# hidiot_1_0_final.net
KiCad netlist of a schematic drawn in EAGLE
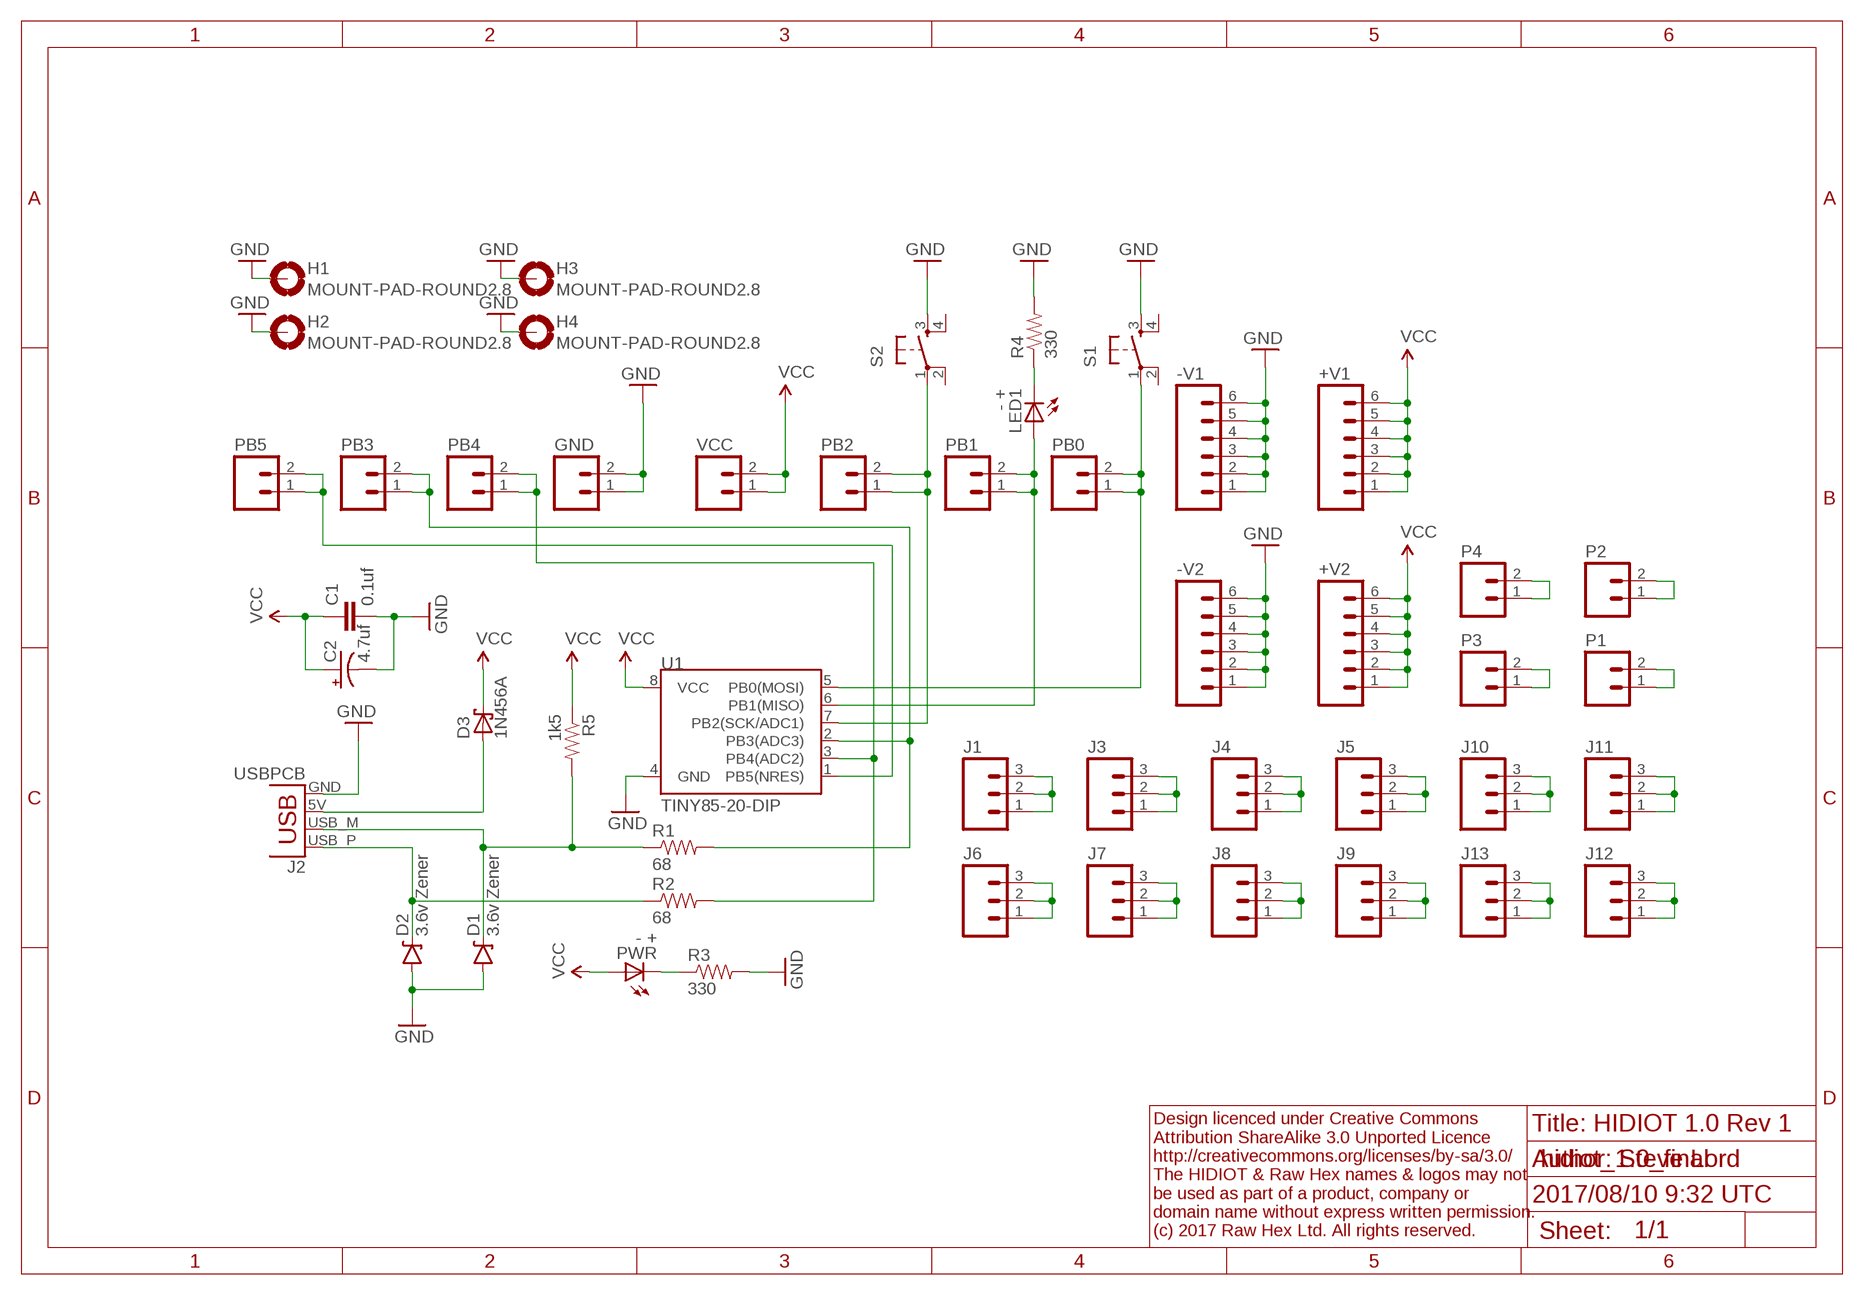
[diagram p0: schematic, sheet 1]

(export (version "E")
  (design (tool "Eeschema 10.0.6"))
  (components
    (comp (ref "+V1")
      (value "M06SILK_FEMALE_PTH")
      (footprint "eagle-import:1X06")
      (libsource (lib "eagle-import") (part "M06SILK_FEMALE_PTH"))
    )
    (comp (ref "+V2")
      (value "M06SILK_FEMALE_PTH")
      (footprint "eagle-import:1X06")
      (libsource (lib "eagle-import") (part "M06SILK_FEMALE_PTH"))
    )
    (comp (ref "-V1")
      (value "M06SILK_FEMALE_PTH")
      (footprint "eagle-import:1X06")
      (libsource (lib "eagle-import") (part "M06SILK_FEMALE_PTH"))
    )
    (comp (ref "-V2")
      (value "M06SILK_FEMALE_PTH")
      (footprint "eagle-import:1X06")
      (libsource (lib "eagle-import") (part "M06SILK_FEMALE_PTH"))
    )
    (comp (ref "C1")
      (value "0.1uf")
      (footprint "eagle-import:CAP-PTH-SMALL-KIT")
      (fields (field (name "MF") "VISHAY") (field (name "MPN") "K104K15X7RF5TH5"))
      (libsource (lib "eagle-import") (part "0.1UF-50V-20%(PTH)KIT-EZ"))
    )
    (comp (ref "C2")
      (value "4.7uf")
      (footprint "eagle-import:CPOL-RADIAL-100UF-25V")
      (fields (field (name "MF") "MULTICOMP") (field (name "MPN") "MCGPR50V475M5X11"))
      (libsource (lib "eagle-import") (part "100UF-25V-20%(PTH)"))
    )
    (comp (ref "D1")
      (value "3.6v Zener")
      (footprint "eagle-import:DIODE-ZENER")
      (fields (field (name "MF") "MULTICOMP") (field (name "MPN") "1N4729A"))
      (libsource (lib "eagle-import") (part "DIODE-ZENERPTH"))
    )
    (comp (ref "D2")
      (value "3.6v Zener")
      (footprint "eagle-import:DIODE-ZENER")
      (fields (field (name "MF") "MULTICOMP") (field (name "MPN") "1N4729A"))
      (libsource (lib "eagle-import") (part "DIODE-ZENERPTH"))
    )
    (comp (ref "D3")
      (value "1N456A")
      (footprint "eagle-import:DIODE_DO35-7")
      (fields (field (name "MF") "FAIRCHILD SEMICONDUCTOR"))
      (libsource (lib "eagle-import") (part "SCHOTTKY-DIODEDO35-7"))
    )
    (comp (ref "GND")
      (value "M02PTH")
      (footprint "eagle-import:1X02")
      (libsource (lib "eagle-import") (part "M02PTH"))
    )
    (comp (ref "H1")
      (value "MOUNT-PAD-ROUND2.8")
      (footprint "eagle-import:2,8-PAD")
      (libsource (lib "eagle-import") (part "MOUNT-PAD-ROUND2.8"))
    )
    (comp (ref "H2")
      (value "MOUNT-PAD-ROUND2.8")
      (footprint "eagle-import:2,8-PAD")
      (libsource (lib "eagle-import") (part "MOUNT-PAD-ROUND2.8"))
    )
    (comp (ref "H3")
      (value "MOUNT-PAD-ROUND2.8")
      (footprint "eagle-import:2,8-PAD")
      (libsource (lib "eagle-import") (part "MOUNT-PAD-ROUND2.8"))
    )
    (comp (ref "H4")
      (value "MOUNT-PAD-ROUND2.8")
      (footprint "eagle-import:2,8-PAD")
      (libsource (lib "eagle-import") (part "MOUNT-PAD-ROUND2.8"))
    )
    (comp (ref "J1")
      (value "M03PTH")
      (footprint "eagle-import:1X03")
      (libsource (lib "eagle-import") (part "M03PTH"))
    )
    (comp (ref "J2")
      (value "USBPCB")
      (footprint "eagle-import:USB-A-PCB")
      (libsource (lib "eagle-import") (part "USBPCB"))
    )
    (comp (ref "J3")
      (value "M03PTH")
      (footprint "eagle-import:1X03")
      (libsource (lib "eagle-import") (part "M03PTH"))
    )
    (comp (ref "J4")
      (value "M03PTH")
      (footprint "eagle-import:1X03")
      (libsource (lib "eagle-import") (part "M03PTH"))
    )
    (comp (ref "J5")
      (value "M03PTH")
      (footprint "eagle-import:1X03")
      (libsource (lib "eagle-import") (part "M03PTH"))
    )
    (comp (ref "J6")
      (value "M03PTH")
      (footprint "eagle-import:1X03")
      (libsource (lib "eagle-import") (part "M03PTH"))
    )
    (comp (ref "J7")
      (value "M03PTH")
      (footprint "eagle-import:1X03")
      (libsource (lib "eagle-import") (part "M03PTH"))
    )
    (comp (ref "J8")
      (value "M03PTH")
      (footprint "eagle-import:1X03")
      (libsource (lib "eagle-import") (part "M03PTH"))
    )
    (comp (ref "J9")
      (value "M03PTH")
      (footprint "eagle-import:1X03")
      (libsource (lib "eagle-import") (part "M03PTH"))
    )
    (comp (ref "J10")
      (value "M03PTH")
      (footprint "eagle-import:1X03")
      (libsource (lib "eagle-import") (part "M03PTH"))
    )
    (comp (ref "J11")
      (value "M03PTH")
      (footprint "eagle-import:1X03")
      (libsource (lib "eagle-import") (part "M03PTH"))
    )
    (comp (ref "J12")
      (value "M03PTH")
      (footprint "eagle-import:1X03")
      (libsource (lib "eagle-import") (part "M03PTH"))
    )
    (comp (ref "J13")
      (value "M03PTH")
      (footprint "eagle-import:1X03")
      (libsource (lib "eagle-import") (part "M03PTH"))
    )
    (comp (ref "LED1")
      (value "- +")
      (footprint "eagle-import:LED3MM")
      (fields (field (name "MF") "AVAGO TECHNOLOGIES") (field (name "MPN") "HLMP-K150"))
      (libsource (lib "eagle-import") (part "LED3MM"))
    )
    (comp (ref "P1")
      (value "M02PTH")
      (footprint "eagle-import:1X02")
      (libsource (lib "eagle-import") (part "M02PTH"))
    )
    (comp (ref "P2")
      (value "M02PTH")
      (footprint "eagle-import:1X02")
      (libsource (lib "eagle-import") (part "M02PTH"))
    )
    (comp (ref "P3")
      (value "M02PTH")
      (footprint "eagle-import:1X02")
      (libsource (lib "eagle-import") (part "M02PTH"))
    )
    (comp (ref "P4")
      (value "M02PTH")
      (footprint "eagle-import:1X02")
      (libsource (lib "eagle-import") (part "M02PTH"))
    )
    (comp (ref "PB0")
      (value "M02PTH")
      (footprint "eagle-import:1X02")
      (libsource (lib "eagle-import") (part "M02PTH"))
    )
    (comp (ref "PB1")
      (value "M02PTH")
      (footprint "eagle-import:1X02")
      (libsource (lib "eagle-import") (part "M02PTH"))
    )
    (comp (ref "PB2")
      (value "M02PTH")
      (footprint "eagle-import:1X02")
      (libsource (lib "eagle-import") (part "M02PTH"))
    )
    (comp (ref "PB3")
      (value "M02PTH")
      (footprint "eagle-import:1X02")
      (libsource (lib "eagle-import") (part "M02PTH"))
    )
    (comp (ref "PB4")
      (value "M02PTH")
      (footprint "eagle-import:1X02")
      (libsource (lib "eagle-import") (part "M02PTH"))
    )
    (comp (ref "PB5")
      (value "M02PTH")
      (footprint "eagle-import:1X02")
      (libsource (lib "eagle-import") (part "M02PTH"))
    )
    (comp (ref "PWR")
      (value "- +")
      (footprint "eagle-import:LED3MM")
      (fields (field (name "MF") "AVAGO TECHNOLOGIES") (field (name "MPN") "HLMP-K150"))
      (libsource (lib "eagle-import") (part "LED3MM"))
    )
    (comp (ref "R1")
      (value "68")
      (footprint "eagle-import:AXIAL-0.4")
      (fields (field (name "MF") "MULTICOMP") (field (name "MPN") "MCF 0.25W 68R"))
      (libsource (lib "eagle-import") (part "RESISTORPTH-1/4W"))
    )
    (comp (ref "R2")
      (value "68")
      (footprint "eagle-import:AXIAL-0.4")
      (fields (field (name "MF") "MULTICOMP") (field (name "MPN") "MCF 0.25W 68R"))
      (libsource (lib "eagle-import") (part "RESISTORPTH-1/4W"))
    )
    (comp (ref "R3")
      (value "330")
      (footprint "eagle-import:AXIAL-0.4")
      (fields (field (name "MF") "MULTICOMP") (field (name "MPN") "MCF 0.25W 68R"))
      (libsource (lib "eagle-import") (part "RESISTORPTH-1/4W"))
    )
    (comp (ref "R4")
      (value "330")
      (footprint "eagle-import:AXIAL-0.4")
      (fields (field (name "MF") "MULTICOMP") (field (name "MPN") "MCF 0.25W 68R"))
      (libsource (lib "eagle-import") (part "RESISTORPTH-1/4W"))
    )
    (comp (ref "R5")
      (value "1k5")
      (footprint "eagle-import:AXIAL-0.4")
      (fields (field (name "MF") "MULTICOMP") (field (name "MPN") "MCF 1W 1K5"))
      (libsource (lib "eagle-import") (part "RESISTORPTH-1/4W"))
    )
    (comp (ref "S1")
      (value "TAC_SWITCHPTH")
      (footprint "eagle-import:TACTILE-PTH")
      (libsource (lib "eagle-import") (part "TAC_SWITCHPTH"))
    )
    (comp (ref "S2")
      (value "TAC_SWITCHPTH")
      (footprint "eagle-import:TACTILE-PTH")
      (libsource (lib "eagle-import") (part "TAC_SWITCHPTH"))
    )
    (comp (ref "U1")
      (value "TINY85-20-DIP")
      (footprint "eagle-import:DIP08")
      (fields (field (name "MF") "ATMEL") (field (name "MPN") "ATTINY85-20PU"))
      (libsource (lib "eagle-import") (part "ATTINY45TINY85-20-DIP"))
    )
    (comp (ref "VCC")
      (value "M02PTH")
      (footprint "eagle-import:1X02")
      (libsource (lib "eagle-import") (part "M02PTH"))
    )
  )
  (nets
    (net (code "1") (name "GND") (class "Default")
      (node (ref "-V1") (pin "1") (pinfunction "1_1") (pintype "passive"))
      (node (ref "-V1") (pin "2") (pinfunction "2_2") (pintype "passive"))
      (node (ref "-V1") (pin "3") (pinfunction "3_3") (pintype "passive"))
      (node (ref "-V1") (pin "4") (pinfunction "4_4") (pintype "passive"))
      (node (ref "-V1") (pin "5") (pinfunction "5_5") (pintype "passive"))
      (node (ref "-V1") (pin "6") (pinfunction "6_6") (pintype "passive"))
      (node (ref "-V2") (pin "1") (pinfunction "1_1") (pintype "passive"))
      (node (ref "-V2") (pin "2") (pinfunction "2_2") (pintype "passive"))
      (node (ref "-V2") (pin "3") (pinfunction "3_3") (pintype "passive"))
      (node (ref "-V2") (pin "4") (pinfunction "4_4") (pintype "passive"))
      (node (ref "-V2") (pin "5") (pinfunction "5_5") (pintype "passive"))
      (node (ref "-V2") (pin "6") (pinfunction "6_6") (pintype "passive"))
      (node (ref "C1") (pin "2") (pinfunction "2_2") (pintype "passive"))
      (node (ref "C2") (pin "2") (pinfunction "-_2") (pintype "passive"))
      (node (ref "D1") (pin "P$2") (pinfunction "A_P$2") (pintype "passive"))
      (node (ref "D2") (pin "P$2") (pinfunction "A_P$2") (pintype "passive"))
      (node (ref "GND") (pin "1") (pinfunction "1_1") (pintype "passive"))
      (node (ref "GND") (pin "2") (pinfunction "2_2") (pintype "passive"))
      (node (ref "H1") (pin "B2,8") (pinfunction "MOUNT_B2,8") (pintype "passive"))
      (node (ref "H2") (pin "B2,8") (pinfunction "MOUNT_B2,8") (pintype "passive"))
      (node (ref "H3") (pin "B2,8") (pinfunction "MOUNT_B2,8") (pintype "passive"))
      (node (ref "H4") (pin "B2,8") (pinfunction "MOUNT_B2,8") (pintype "passive"))
      (node (ref "J2") (pin "GND") (pinfunction "GND_GND") (pintype "bidirectional"))
      (node (ref "R3") (pin "P$2") (pinfunction "2_P$2") (pintype "passive"))
      (node (ref "R4") (pin "P$2") (pinfunction "2_P$2") (pintype "passive"))
      (node (ref "S1") (pin "3") (pinfunction "3_3") (pintype "passive"))
      (node (ref "S2") (pin "3") (pinfunction "3_3") (pintype "passive"))
      (node (ref "U1") (pin "4") (pinfunction "GND_4") (pintype "bidirectional"))
    )
    (net (code "2") (name "Net-(D1-C)") (class "Default")
      (node (ref "D1") (pin "P$1") (pinfunction "C_P$1") (pintype "passive"))
      (node (ref "J2") (pin "USB_M") (pinfunction "D-_USB_M") (pintype "bidirectional"))
      (node (ref "R1") (pin "P$1") (pinfunction "1_P$1") (pintype "passive"))
      (node (ref "R5") (pin "P$2") (pinfunction "2_P$2") (pintype "passive"))
    )
    (net (code "3") (name "Net-(D2-C)") (class "Default")
      (node (ref "D2") (pin "P$1") (pinfunction "C_P$1") (pintype "passive"))
      (node (ref "J2") (pin "USB_P") (pinfunction "D+_USB_P") (pintype "bidirectional"))
      (node (ref "R2") (pin "P$1") (pinfunction "1_P$1") (pintype "passive"))
    )
    (net (code "4") (name "Net-(D3-C)") (class "Default")
      (node (ref "D3") (pin "A") (pinfunction "C_A") (pintype "passive"))
      (node (ref "J2") (pin "5V") (pinfunction "VBUS_5V") (pintype "bidirectional"))
    )
    (net (code "5") (name "Net-(J1-Pad1)") (class "Default")
      (node (ref "J1") (pin "1") (pinfunction "1_1") (pintype "passive"))
      (node (ref "J1") (pin "2") (pinfunction "2_2") (pintype "passive"))
      (node (ref "J1") (pin "3") (pinfunction "3_3") (pintype "passive"))
    )
    (net (code "6") (name "Net-(J3-Pad1)") (class "Default")
      (node (ref "J3") (pin "1") (pinfunction "1_1") (pintype "passive"))
      (node (ref "J3") (pin "2") (pinfunction "2_2") (pintype "passive"))
      (node (ref "J3") (pin "3") (pinfunction "3_3") (pintype "passive"))
    )
    (net (code "7") (name "Net-(J4-Pad1)") (class "Default")
      (node (ref "J4") (pin "1") (pinfunction "1_1") (pintype "passive"))
      (node (ref "J4") (pin "2") (pinfunction "2_2") (pintype "passive"))
      (node (ref "J4") (pin "3") (pinfunction "3_3") (pintype "passive"))
    )
    (net (code "8") (name "Net-(J5-Pad1)") (class "Default")
      (node (ref "J5") (pin "1") (pinfunction "1_1") (pintype "passive"))
      (node (ref "J5") (pin "2") (pinfunction "2_2") (pintype "passive"))
      (node (ref "J5") (pin "3") (pinfunction "3_3") (pintype "passive"))
    )
    (net (code "9") (name "Net-(J6-Pad1)") (class "Default")
      (node (ref "J6") (pin "1") (pinfunction "1_1") (pintype "passive"))
      (node (ref "J6") (pin "2") (pinfunction "2_2") (pintype "passive"))
      (node (ref "J6") (pin "3") (pinfunction "3_3") (pintype "passive"))
    )
    (net (code "10") (name "Net-(J7-Pad1)") (class "Default")
      (node (ref "J7") (pin "1") (pinfunction "1_1") (pintype "passive"))
      (node (ref "J7") (pin "2") (pinfunction "2_2") (pintype "passive"))
      (node (ref "J7") (pin "3") (pinfunction "3_3") (pintype "passive"))
    )
    (net (code "11") (name "Net-(J8-Pad1)") (class "Default")
      (node (ref "J8") (pin "1") (pinfunction "1_1") (pintype "passive"))
      (node (ref "J8") (pin "2") (pinfunction "2_2") (pintype "passive"))
      (node (ref "J8") (pin "3") (pinfunction "3_3") (pintype "passive"))
    )
    (net (code "12") (name "Net-(J9-Pad1)") (class "Default")
      (node (ref "J9") (pin "1") (pinfunction "1_1") (pintype "passive"))
      (node (ref "J9") (pin "2") (pinfunction "2_2") (pintype "passive"))
      (node (ref "J9") (pin "3") (pinfunction "3_3") (pintype "passive"))
    )
    (net (code "13") (name "Net-(J10-Pad1)") (class "Default")
      (node (ref "J10") (pin "1") (pinfunction "1_1") (pintype "passive"))
      (node (ref "J10") (pin "2") (pinfunction "2_2") (pintype "passive"))
      (node (ref "J10") (pin "3") (pinfunction "3_3") (pintype "passive"))
    )
    (net (code "14") (name "Net-(J11-Pad1)") (class "Default")
      (node (ref "J11") (pin "1") (pinfunction "1_1") (pintype "passive"))
      (node (ref "J11") (pin "2") (pinfunction "2_2") (pintype "passive"))
      (node (ref "J11") (pin "3") (pinfunction "3_3") (pintype "passive"))
    )
    (net (code "15") (name "Net-(J12-Pad1)") (class "Default")
      (node (ref "J12") (pin "1") (pinfunction "1_1") (pintype "passive"))
      (node (ref "J12") (pin "2") (pinfunction "2_2") (pintype "passive"))
      (node (ref "J12") (pin "3") (pinfunction "3_3") (pintype "passive"))
    )
    (net (code "16") (name "Net-(J13-Pad1)") (class "Default")
      (node (ref "J13") (pin "1") (pinfunction "1_1") (pintype "passive"))
      (node (ref "J13") (pin "2") (pinfunction "2_2") (pintype "passive"))
      (node (ref "J13") (pin "3") (pinfunction "3_3") (pintype "passive"))
    )
    (net (code "17") (name "Net-(LED1-C)") (class "Default")
      (node (ref "LED1") (pin "K") (pinfunction "C_K") (pintype "passive"))
      (node (ref "R4") (pin "P$1") (pinfunction "1_P$1") (pintype "passive"))
    )
    (net (code "18") (name "Net-(P1-Pad1)") (class "Default")
      (node (ref "P1") (pin "1") (pinfunction "1_1") (pintype "passive"))
      (node (ref "P1") (pin "2") (pinfunction "2_2") (pintype "passive"))
    )
    (net (code "19") (name "Net-(P2-Pad1)") (class "Default")
      (node (ref "P2") (pin "1") (pinfunction "1_1") (pintype "passive"))
      (node (ref "P2") (pin "2") (pinfunction "2_2") (pintype "passive"))
    )
    (net (code "20") (name "Net-(P3-Pad1)") (class "Default")
      (node (ref "P3") (pin "1") (pinfunction "1_1") (pintype "passive"))
      (node (ref "P3") (pin "2") (pinfunction "2_2") (pintype "passive"))
    )
    (net (code "21") (name "Net-(P4-Pad1)") (class "Default")
      (node (ref "P4") (pin "1") (pinfunction "1_1") (pintype "passive"))
      (node (ref "P4") (pin "2") (pinfunction "2_2") (pintype "passive"))
    )
    (net (code "22") (name "Net-(PWR-C)") (class "Default")
      (node (ref "PWR") (pin "K") (pinfunction "C_K") (pintype "passive"))
      (node (ref "R3") (pin "P$1") (pinfunction "1_P$1") (pintype "passive"))
    )
    (net (code "23") (name "Net-(R1-2)") (class "Default")
      (node (ref "PB3") (pin "1") (pinfunction "1_1") (pintype "passive"))
      (node (ref "PB3") (pin "2") (pinfunction "2_2") (pintype "passive"))
      (node (ref "R1") (pin "P$2") (pinfunction "2_P$2") (pintype "passive"))
      (node (ref "U1") (pin "2") (pinfunction "PB3(ADC3)_2") (pintype "bidirectional"))
    )
    (net (code "24") (name "Net-(R2-2)") (class "Default")
      (node (ref "PB4") (pin "1") (pinfunction "1_1") (pintype "passive"))
      (node (ref "PB4") (pin "2") (pinfunction "2_2") (pintype "passive"))
      (node (ref "R2") (pin "P$2") (pinfunction "2_P$2") (pintype "passive"))
      (node (ref "U1") (pin "3") (pinfunction "PB4(ADC2)_3") (pintype "bidirectional"))
    )
    (net (code "25") (name "Net-(U1-PB0(MOSI))") (class "Default")
      (node (ref "PB0") (pin "1") (pinfunction "1_1") (pintype "passive"))
      (node (ref "PB0") (pin "2") (pinfunction "2_2") (pintype "passive"))
      (node (ref "S1") (pin "1") (pinfunction "1_1") (pintype "passive"))
      (node (ref "U1") (pin "5") (pinfunction "PB0(MOSI)_5") (pintype "bidirectional"))
    )
    (net (code "26") (name "Net-(U1-PB1(MISO))") (class "Default")
      (node (ref "LED1") (pin "A") (pinfunction "A_A") (pintype "passive"))
      (node (ref "PB1") (pin "1") (pinfunction "1_1") (pintype "passive"))
      (node (ref "PB1") (pin "2") (pinfunction "2_2") (pintype "passive"))
      (node (ref "U1") (pin "6") (pinfunction "PB1(MISO)_6") (pintype "bidirectional"))
    )
    (net (code "27") (name "Net-(U1-PB2(SCK{slash}ADC1))") (class "Default")
      (node (ref "PB2") (pin "1") (pinfunction "1_1") (pintype "passive"))
      (node (ref "PB2") (pin "2") (pinfunction "2_2") (pintype "passive"))
      (node (ref "S2") (pin "1") (pinfunction "1_1") (pintype "passive"))
      (node (ref "U1") (pin "7") (pinfunction "PB2(SCK/ADC1)_7") (pintype "bidirectional"))
    )
    (net (code "28") (name "Net-(U1-PB5(NRES))") (class "Default")
      (node (ref "PB5") (pin "1") (pinfunction "1_1") (pintype "passive"))
      (node (ref "PB5") (pin "2") (pinfunction "2_2") (pintype "passive"))
      (node (ref "U1") (pin "1") (pinfunction "PB5(NRES)_1") (pintype "bidirectional"))
    )
    (net (code "29") (name "VCC") (class "Default")
      (node (ref "+V1") (pin "1") (pinfunction "1_1") (pintype "passive"))
      (node (ref "+V1") (pin "2") (pinfunction "2_2") (pintype "passive"))
      (node (ref "+V1") (pin "3") (pinfunction "3_3") (pintype "passive"))
      (node (ref "+V1") (pin "4") (pinfunction "4_4") (pintype "passive"))
      (node (ref "+V1") (pin "5") (pinfunction "5_5") (pintype "passive"))
      (node (ref "+V1") (pin "6") (pinfunction "6_6") (pintype "passive"))
      (node (ref "+V2") (pin "1") (pinfunction "1_1") (pintype "passive"))
      (node (ref "+V2") (pin "2") (pinfunction "2_2") (pintype "passive"))
      (node (ref "+V2") (pin "3") (pinfunction "3_3") (pintype "passive"))
      (node (ref "+V2") (pin "4") (pinfunction "4_4") (pintype "passive"))
      (node (ref "+V2") (pin "5") (pinfunction "5_5") (pintype "passive"))
      (node (ref "+V2") (pin "6") (pinfunction "6_6") (pintype "passive"))
      (node (ref "C1") (pin "1") (pinfunction "1_1") (pintype "passive"))
      (node (ref "C2") (pin "1") (pinfunction "+_1") (pintype "passive"))
      (node (ref "D3") (pin "C") (pinfunction "A_C") (pintype "passive"))
      (node (ref "PWR") (pin "A") (pinfunction "A_A") (pintype "passive"))
      (node (ref "R5") (pin "P$1") (pinfunction "1_P$1") (pintype "passive"))
      (node (ref "U1") (pin "8") (pinfunction "VCC_8") (pintype "bidirectional"))
      (node (ref "VCC") (pin "1") (pinfunction "1_1") (pintype "passive"))
      (node (ref "VCC") (pin "2") (pinfunction "2_2") (pintype "passive"))
    )
    (net (code "30") (name "unconnected-(S1-Pad2)") (class "Default")
      (node (ref "S1") (pin "2") (pinfunction "2_2") (pintype "passive"))
    )
    (net (code "31") (name "unconnected-(S1-Pad4)") (class "Default")
      (node (ref "S1") (pin "4") (pinfunction "4_4") (pintype "passive"))
    )
    (net (code "32") (name "unconnected-(S2-Pad2)") (class "Default")
      (node (ref "S2") (pin "2") (pinfunction "2_2") (pintype "passive"))
    )
    (net (code "33") (name "unconnected-(S2-Pad4)") (class "Default")
      (node (ref "S2") (pin "4") (pinfunction "4_4") (pintype "passive"))
    )
  )
)
